# external_connector.net
KiCad netlist of a schematic drawn in Altium Designer
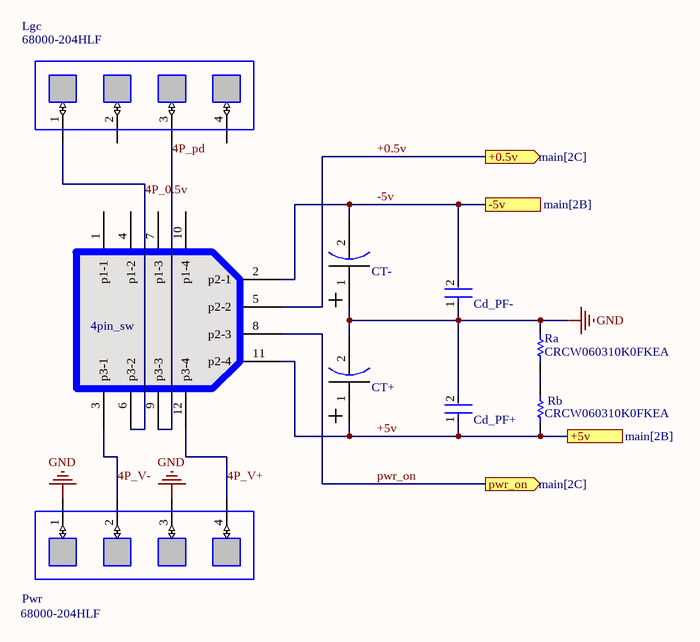
[diagram p0: external_connector.SchDoc]

(export (version "E")
  (design (tool "Eeschema 10.0.6"))
  (components
    (comp (ref "4pin_sw")
      (value "1004P3T2B4M7QE")
      (footprint "1004P3T2B4M7QE-Footprint-1")
      (description "ESWCH 1004P3T2B4M7QE Switches > Toggle > Mini Toggle Switch")
      (libsource (lib "kevin kim") (part "1004P3T2B4M7QE-Symbol-1"))
    )
    (comp (ref "Cd_PF+")
      (value "C0402C104K4RACTU")
      (footprint "FP-C0402-BB-MFG")
      (description "CAP CER 0.1UF 16V X7R 0402")
      (fields
        (field (name "TOLERANCE") "0.1")
        (field (name "OCTOPART") "https://octopart.com/c0402c104k4ractu-kemet-94158")
      )
      (libsource (lib "Altium Content Vault") (part "b4654b650e69147ec39a6b967a45e02"))
    )
    (comp (ref "Cd_PF-")
      (value "C0402C104K4RACTU")
      (footprint "FP-C0402-BB-MFG")
      (description "CAP CER 0.1UF 16V X7R 0402")
      (fields
        (field (name "TOLERANCE") "0.1")
        (field (name "OCTOPART") "https://octopart.com/c0402c104k4ractu-kemet-94158")
      )
      (libsource (lib "Altium Content Vault") (part "b4654b650e69147ec39a6b967a45e02"))
    )
    (comp (ref "CT+")
      (value "597D107X0040H2T")
      (footprint "597D107X0040H2T-Footprint-1")
      (description "Solid Tantalum Chip Capacitors, Ultra-Low ESR, Conformal Coated, Maximum CV")
      (libsource (lib "kevin kim") (part "597D107X0040H2T-Symbol-1"))
    )
    (comp (ref "CT-")
      (value "597D107X0040H2T")
      (footprint "597D107X0040H2T-Footprint-1")
      (description "Solid Tantalum Chip Capacitors, Ultra-Low ESR, Conformal Coated, Maximum CV")
      (libsource (lib "kevin kim") (part "597D107X0040H2T-Symbol-1"))
    )
    (comp (ref "Lgc")
      (value "68000-204HLF")
      (footprint "68000-204HLF-Footprint-1")
      (description "Conn Unshrouded Header HDR 4 POS 2.54mm Solder ST Top Entry Thru-Hole BergStik® Bulk")
      (libsource (lib "kevin kim") (part "68000-204HLF"))
    )
    (comp (ref "Pwr")
      (value "68000-204HLF")
      (footprint "68000-204HLF-Footprint-1")
      (description "Conn Unshrouded Header HDR 4 POS 2.54mm Solder ST Top Entry Thru-Hole BergStik® Bulk")
      (libsource (lib "kevin kim") (part "68000-204HLF"))
    )
    (comp (ref "Ra")
      (value "CRCW060310K0FKEA")
      (footprint "RESC1609X50X30NL8T20")
      (description "Chip Resistor, 10 KOhm, +/- 1%, 100 mW, -55 to 155 degC, 0603 (1608 Metric), RoHS, Tape and Reel")
      (fields (field (name "MANUFACTURER") "Vishay Semiconductor"))
      (libsource (lib "Altium Content Vault") (part "RES-2"))
    )
    (comp (ref "Rb")
      (value "CRCW060310K0FKEA")
      (footprint "RESC1609X50X30NL8T20")
      (description "Chip Resistor, 10 KOhm, +/- 1%, 100 mW, -55 to 155 degC, 0603 (1608 Metric), RoHS, Tape and Reel")
      (fields (field (name "MANUFACTURER") "Vishay Semiconductor"))
      (libsource (lib "Altium Content Vault") (part "RES-2"))
    )
  )
  (nets
    (net (code "1") (name "/+0.5v") (class "Default")
      (node (ref "4pin_sw") (pin "5") (pinfunction "p2-2_5") (pintype "passive"))
    )
    (net (code "2") (name "/+5v") (class "Default")
      (node (ref "4pin_sw") (pin "11") (pinfunction "p2-4_11") (pintype "passive"))
      (node (ref "CT+") (pin "1") (pinfunction "pos_1") (pintype "passive"))
      (node (ref "Cd_PF+") (pin "1") (pinfunction "1_1") (pintype "passive"))
      (node (ref "Rb") (pin "2") (pinfunction "2_2") (pintype "passive"))
    )
    (net (code "3") (name "/-5v") (class "Default")
      (node (ref "4pin_sw") (pin "2") (pinfunction "p2-1_2") (pintype "passive"))
      (node (ref "CT-") (pin "2") (pinfunction "neg_2") (pintype "passive"))
      (node (ref "Cd_PF-") (pin "2") (pinfunction "2_2") (pintype "passive"))
    )
    (net (code "4") (name "/4P_0.5v") (class "Default")
      (node (ref "4pin_sw") (pin "6") (pinfunction "p3-2_6") (pintype "passive"))
      (node (ref "Lgc") (pin "1") (pinfunction "pin1_1") (pintype "bidirectional"))
    )
    (net (code "5") (name "/4P_V+") (class "Default")
      (node (ref "4pin_sw") (pin "12") (pinfunction "p3-4_12") (pintype "passive"))
      (node (ref "Pwr") (pin "4") (pinfunction "pin1_4") (pintype "bidirectional"))
    )
    (net (code "6") (name "/4P_V-") (class "Default")
      (node (ref "4pin_sw") (pin "3") (pinfunction "p3-1_3") (pintype "passive"))
      (node (ref "Pwr") (pin "2") (pinfunction "pin1_2") (pintype "bidirectional"))
    )
    (net (code "7") (name "/4P_pd") (class "Default")
      (node (ref "4pin_sw") (pin "9") (pinfunction "p3-3_9") (pintype "passive"))
      (node (ref "Lgc") (pin "3") (pinfunction "pin1_3") (pintype "bidirectional"))
    )
    (net (code "8") (name "/pwr_on") (class "Default")
      (node (ref "4pin_sw") (pin "8") (pinfunction "p2-3_8") (pintype "passive"))
    )
    (net (code "9") (name "GND") (class "Default")
      (node (ref "CT+") (pin "2") (pinfunction "neg_2") (pintype "passive"))
      (node (ref "CT-") (pin "1") (pinfunction "pos_1") (pintype "passive"))
      (node (ref "Cd_PF+") (pin "2") (pinfunction "2_2") (pintype "passive"))
      (node (ref "Cd_PF-") (pin "1") (pinfunction "1_1") (pintype "passive"))
      (node (ref "Pwr") (pin "1") (pinfunction "pin1_1") (pintype "bidirectional"))
      (node (ref "Pwr") (pin "3") (pinfunction "pin1_3") (pintype "bidirectional"))
      (node (ref "Ra") (pin "1") (pinfunction "1_1") (pintype "passive"))
    )
    (net (code "10") (name "Net-(Ra-Pad2)") (class "Default")
      (node (ref "Ra") (pin "2") (pinfunction "2_2") (pintype "passive"))
      (node (ref "Rb") (pin "1") (pinfunction "1_1") (pintype "passive"))
    )
    (net (code "11") (name "unconnected-(4pin_sw-p1-1-Pad1)") (class "Default")
      (node (ref "4pin_sw") (pin "1") (pinfunction "p1-1_1") (pintype "passive"))
    )
    (net (code "12") (name "unconnected-(4pin_sw-p1-2-Pad4)") (class "Default")
      (node (ref "4pin_sw") (pin "4") (pinfunction "p1-2_4") (pintype "passive"))
    )
    (net (code "13") (name "unconnected-(4pin_sw-p1-3-Pad7)") (class "Default")
      (node (ref "4pin_sw") (pin "7") (pinfunction "p1-3_7") (pintype "passive"))
    )
    (net (code "14") (name "unconnected-(4pin_sw-p1-4-Pad10)") (class "Default")
      (node (ref "4pin_sw") (pin "10") (pinfunction "p1-4_10") (pintype "passive"))
    )
    (net (code "15") (name "unconnected-(Lgc-pin1-Pad2)") (class "Default")
      (node (ref "Lgc") (pin "2") (pinfunction "pin1_2") (pintype "bidirectional"))
    )
    (net (code "16") (name "unconnected-(Lgc-pin1-Pad4)") (class "Default")
      (node (ref "Lgc") (pin "4") (pinfunction "pin1_4") (pintype "bidirectional"))
    )
  )
)
